# SCH_noobie-NFC_2024-11-29.net
KiCad netlist of a schematic drawn in EasyEDA
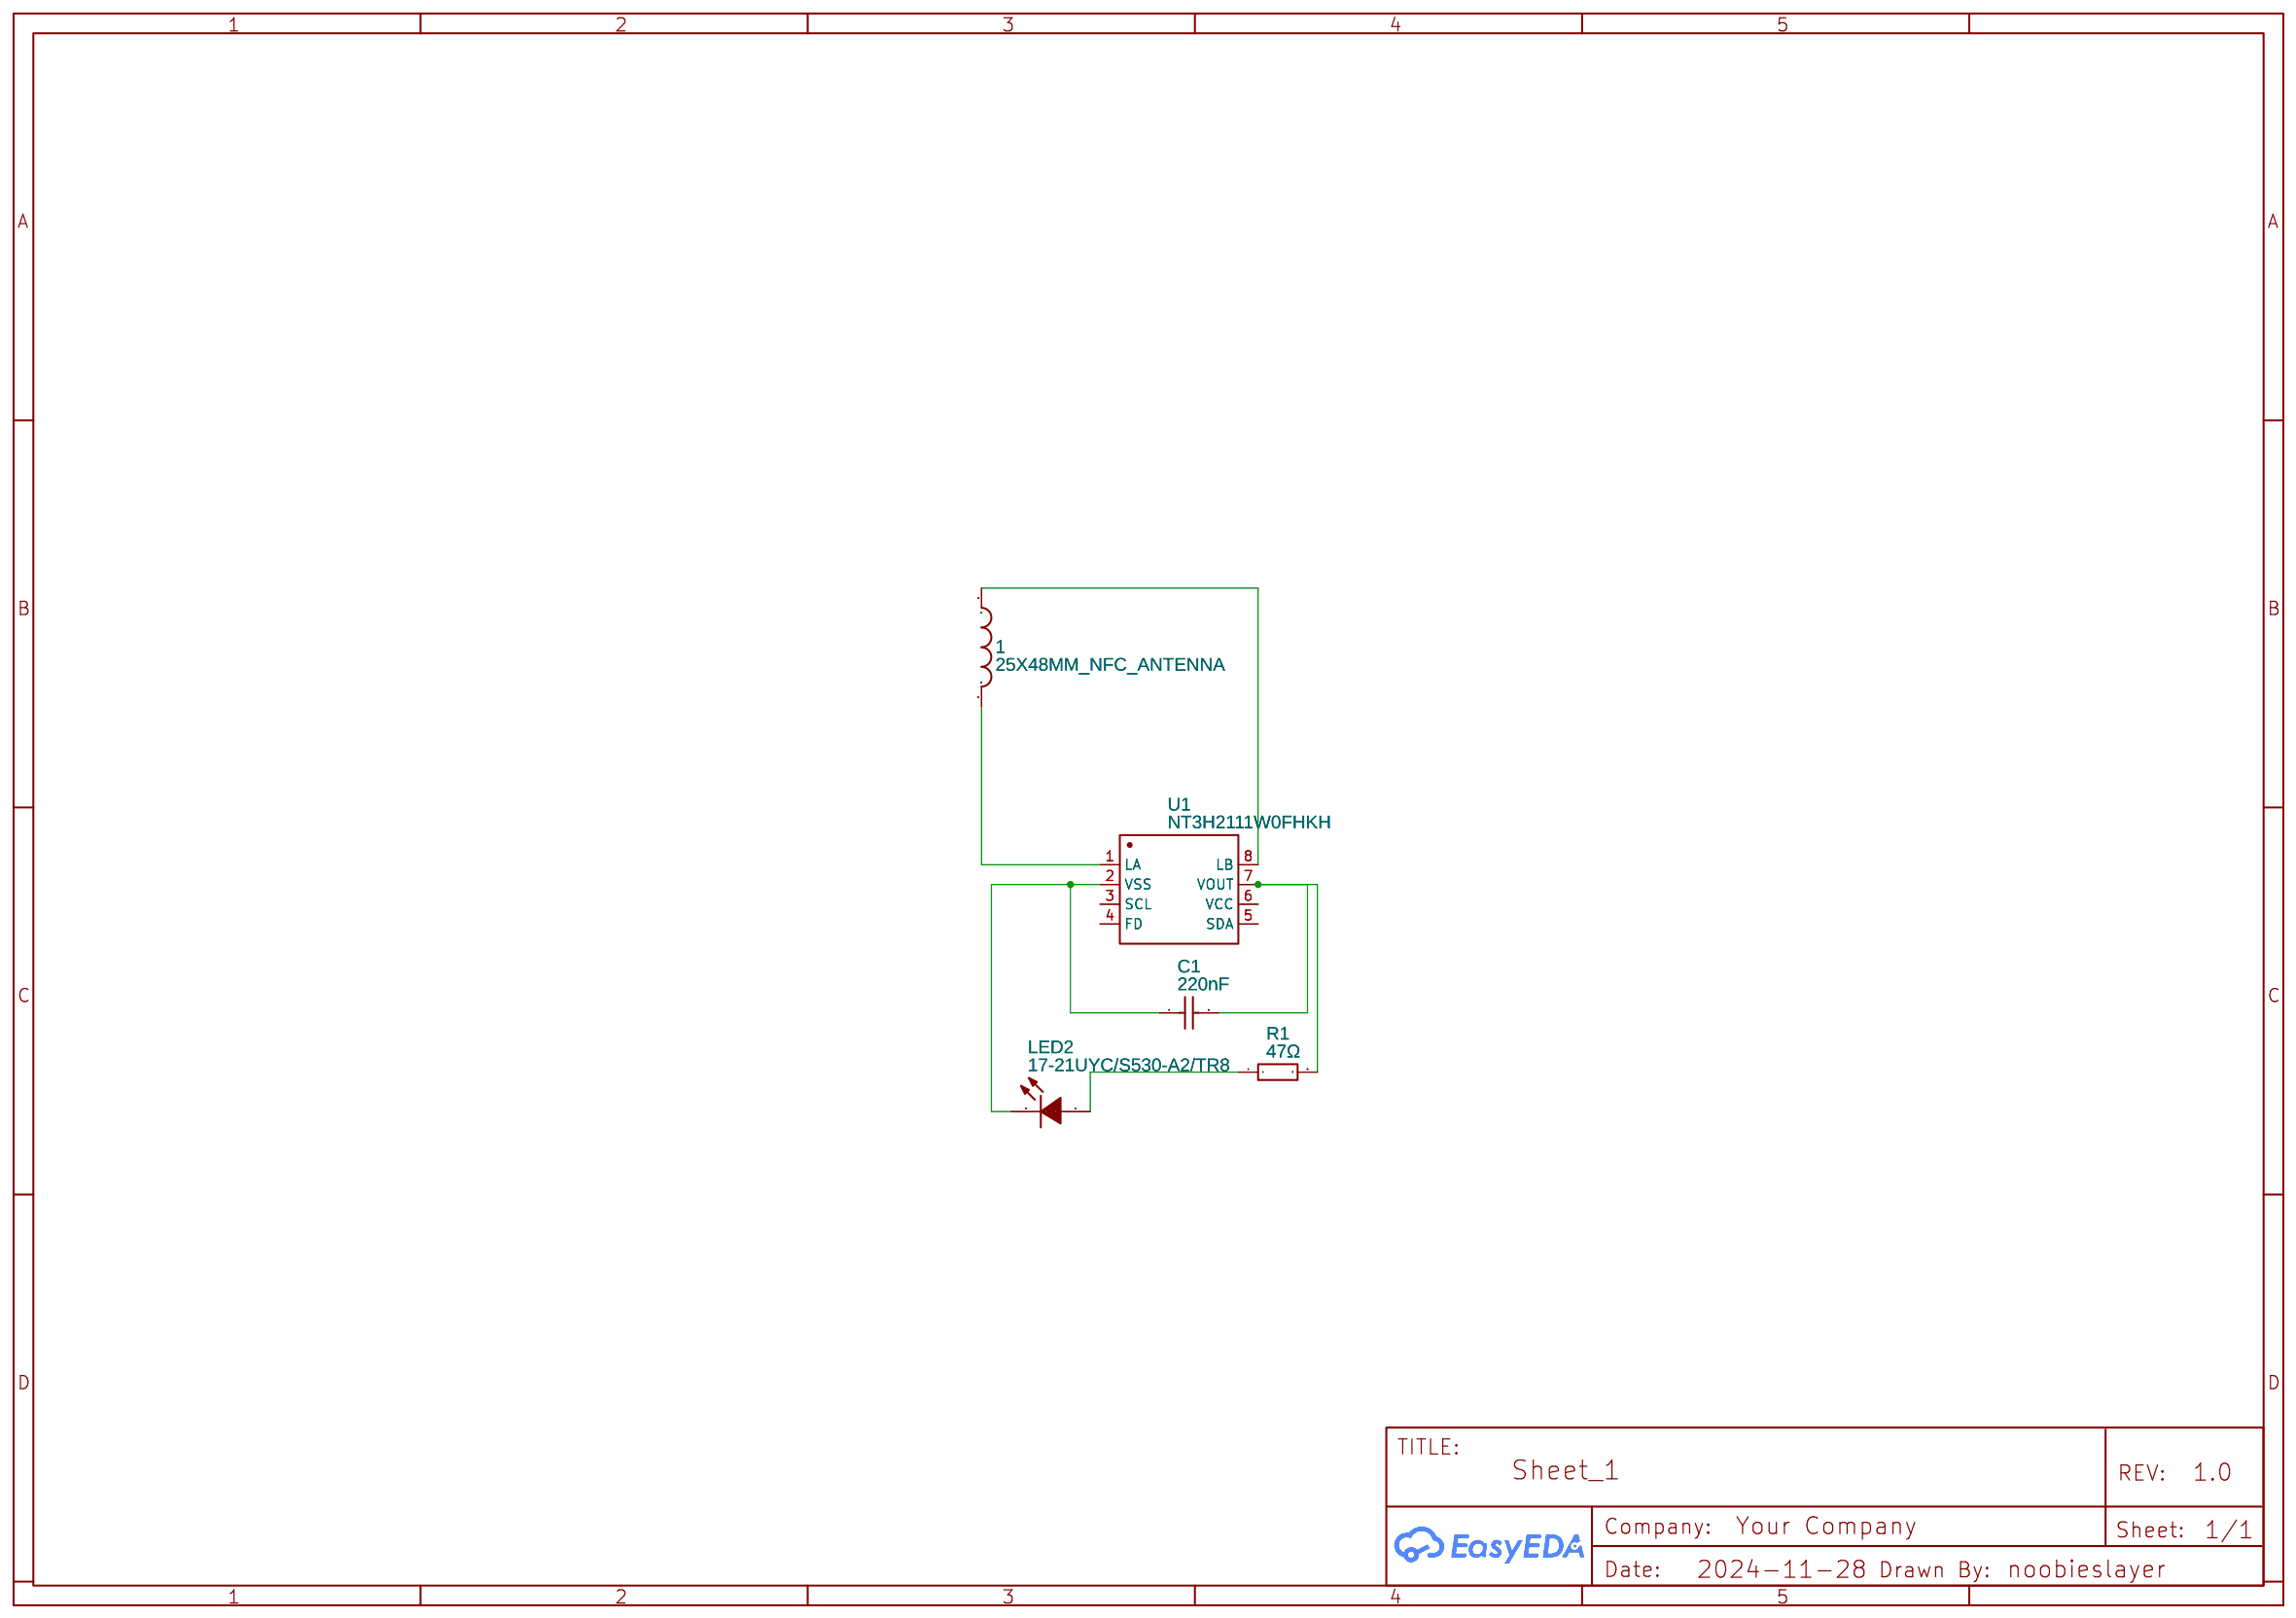
[diagram p0: schematic sheet]

(export (version "E")
  (design (tool "Eeschema 10.0.6"))
  (components
    (comp (ref "1") (value "25X48MM_NFC_ANTENNA") (libsource (lib "") (part "25X48MM_NFC_ANTENNA")))
    (comp (ref "C1")
      (value "220nF")
      (fields
        (field (name "Manufacturer Part") "CL10B224KA8NNNC")
        (field (name "Manufacturer") "SAMSUNG(三星)")
      )
      (libsource (lib "") (part "CL10B224KA8NNNC"))
    )
    (comp (ref "LED2")
      (value "17-21UYC/S530-A2/TR8")
      (fields (field (name "Manufacturer") "EVERLIGHT(亿光)"))
      (libsource (lib "") (part "17-21UYC/S530-A2/TR8"))
    )
    (comp (ref "R1")
      (value "47Ω")
      (fields
        (field (name "Manufacturer Part") "0603WAF470JT5E")
        (field (name "Manufacturer") "UNI-ROYAL(厚声)")
      )
      (libsource (lib "") (part "0603WAF470JT5E"))
    )
    (comp (ref "U1")
      (value "NT3H2111W0FHKH")
      (fields (field (name "Manufacturer") "NXP(恩智浦)"))
      (libsource (lib "") (part "NT3H2111W0FHKH"))
    )
  )
  (nets
    (net (code "1") (name "Net-(LED2-+)") (class "Default")
      (node (ref "LED2") (pin "1") (pinfunction "+_1") (pintype "unspecified"))
      (node (ref "R1") (pin "1") (pinfunction "1_1") (pintype "input"))
    )
    (net (code "2") (name "Net-(LED2--)") (class "Default")
      (node (ref "C1") (pin "1") (pinfunction "1_1") (pintype "input"))
      (node (ref "LED2") (pin "2") (pinfunction "-_2") (pintype "unspecified"))
      (node (ref "U1") (pin "2") (pinfunction "VSS_2") (pintype "unspecified"))
    )
    (net (code "3") (name "Net-(U1-LA)") (class "Default")
      (node (ref "1") (pin "P$2") (pinfunction "P$2_P$2") (pintype "bidirectional"))
      (node (ref "U1") (pin "1") (pinfunction "LA_1") (pintype "unspecified"))
    )
    (net (code "4") (name "Net-(U1-LB)") (class "Default")
      (node (ref "1") (pin "P$1") (pinfunction "P$1_P$1") (pintype "bidirectional"))
      (node (ref "U1") (pin "8") (pinfunction "LB_8") (pintype "unspecified"))
    )
    (net (code "5") (name "Net-(U1-VOUT)") (class "Default")
      (node (ref "C1") (pin "2") (pinfunction "2_2") (pintype "input"))
      (node (ref "R1") (pin "2") (pinfunction "2_2") (pintype "input"))
      (node (ref "U1") (pin "7") (pinfunction "VOUT_7") (pintype "unspecified"))
    )
    (net (code "6") (name "unconnected-(U1-FD-Pad4)") (class "Default")
      (node (ref "U1") (pin "4") (pinfunction "FD_4") (pintype "unspecified"))
    )
    (net (code "7") (name "unconnected-(U1-SCL-Pad3)") (class "Default")
      (node (ref "U1") (pin "3") (pinfunction "SCL_3") (pintype "unspecified"))
    )
    (net (code "8") (name "unconnected-(U1-SDA-Pad5)") (class "Default")
      (node (ref "U1") (pin "5") (pinfunction "SDA_5") (pintype "unspecified"))
    )
    (net (code "9") (name "unconnected-(U1-VCC-Pad6)") (class "Default")
      (node (ref "U1") (pin "6") (pinfunction "VCC_6") (pintype "unspecified"))
    )
  )
)
